# matam_qfn20.net
KiCad netlist of a schematic drawn in EAGLE
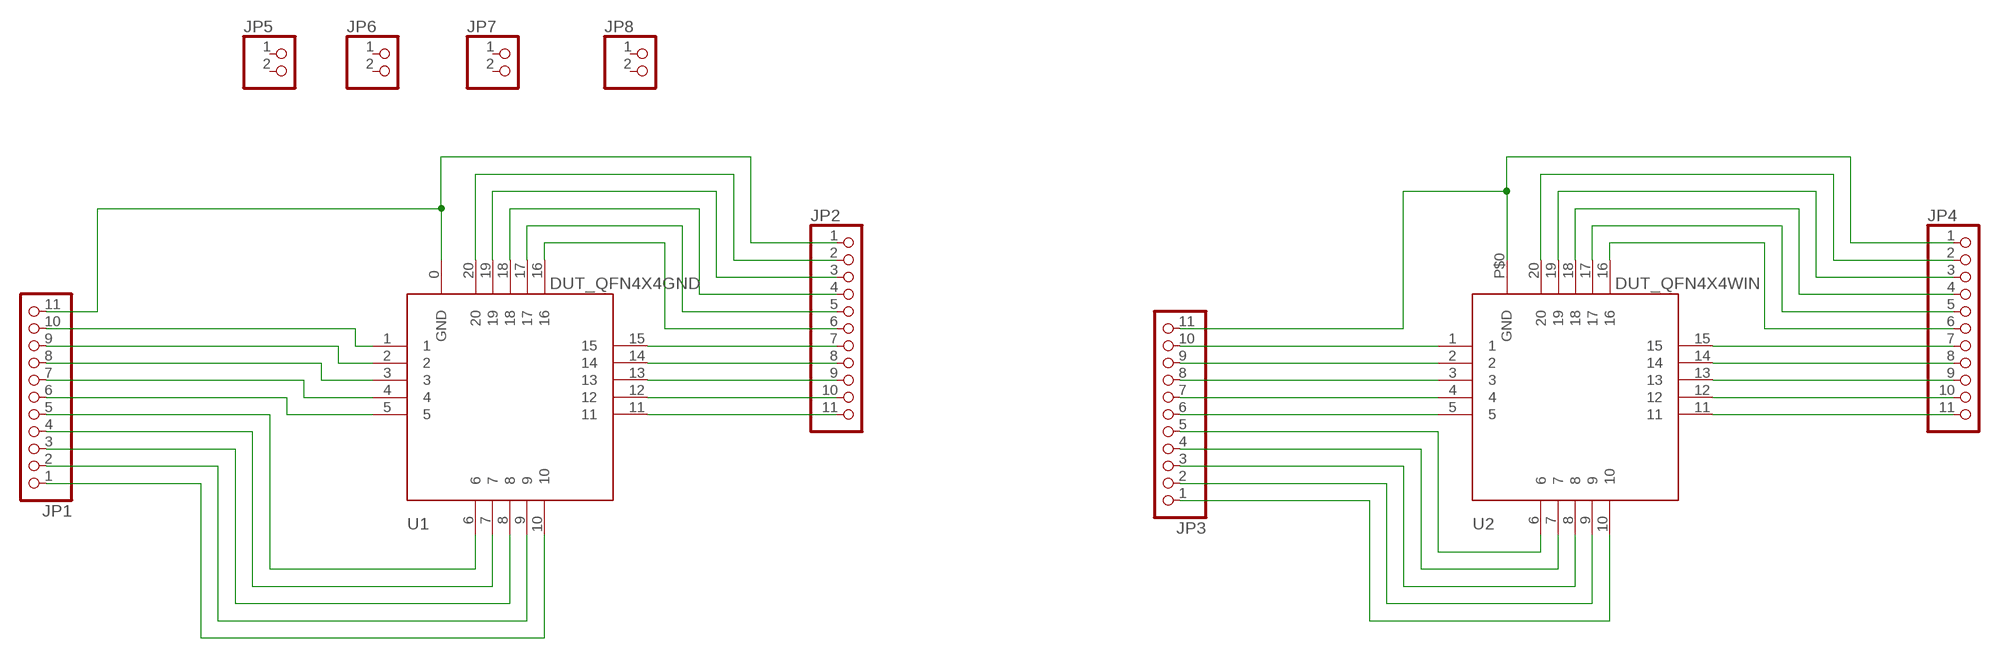
[diagram p0: schematic, sheet 1]

(export (version "E")
  (design (tool "Eeschema 10.0.6"))
  (components
    (comp (ref "JP1")
      (value "PINHD-1X11")
      (footprint "eagle-import:1X11")
      (libsource (lib "eagle-import") (part "PINHD-1X11"))
    )
    (comp (ref "JP2")
      (value "PINHD-1X11")
      (footprint "eagle-import:1X11")
      (libsource (lib "eagle-import") (part "PINHD-1X11"))
    )
    (comp (ref "JP3")
      (value "PINHD-1X11")
      (footprint "eagle-import:1X11")
      (libsource (lib "eagle-import") (part "PINHD-1X11"))
    )
    (comp (ref "JP4")
      (value "PINHD-1X11")
      (footprint "eagle-import:1X11")
      (libsource (lib "eagle-import") (part "PINHD-1X11"))
    )
    (comp (ref "JP5")
      (value "PINHD-1X2/90")
      (footprint "eagle-import:1X02_90")
      (libsource (lib "eagle-import") (part "PINHD-1X2/90"))
    )
    (comp (ref "JP6")
      (value "PINHD-1X2/90")
      (footprint "eagle-import:1X02_90")
      (libsource (lib "eagle-import") (part "PINHD-1X2/90"))
    )
    (comp (ref "JP7")
      (value "PINHD-1X2/90")
      (footprint "eagle-import:1X02_90")
      (libsource (lib "eagle-import") (part "PINHD-1X2/90"))
    )
    (comp (ref "JP8")
      (value "PINHD-1X2/90")
      (footprint "eagle-import:1X02_90")
      (libsource (lib "eagle-import") (part "PINHD-1X2/90"))
    )
    (comp (ref "U1")
      (value "DUT_QFN4X4GND")
      (footprint "eagle-import:QFN20_4X4_GND")
      (libsource (lib "eagle-import") (part "DUT_QFN4X4GND"))
    )
    (comp (ref "U2")
      (value "DUT_QFN4X4WIN")
      (footprint "eagle-import:QFN20_4X4_WINDOW")
      (libsource (lib "eagle-import") (part "DUT_QFN4X4WIN"))
    )
  )
  (nets
    (net (code "1") (name "Net-(JP1-Pad1)") (class "Default")
      (node (ref "JP1") (pin "1") (pinfunction "1_1") (pintype "passive"))
      (node (ref "U1") (pin "10") (pinfunction "10_10") (pintype "bidirectional"))
    )
    (net (code "2") (name "Net-(JP1-Pad2)") (class "Default")
      (node (ref "JP1") (pin "2") (pinfunction "2_2") (pintype "passive"))
      (node (ref "U1") (pin "9") (pinfunction "9_9") (pintype "bidirectional"))
    )
    (net (code "3") (name "Net-(JP1-Pad3)") (class "Default")
      (node (ref "JP1") (pin "3") (pinfunction "3_3") (pintype "passive"))
      (node (ref "U1") (pin "8") (pinfunction "8_8") (pintype "bidirectional"))
    )
    (net (code "4") (name "Net-(JP1-Pad4)") (class "Default")
      (node (ref "JP1") (pin "4") (pinfunction "4_4") (pintype "passive"))
      (node (ref "U1") (pin "7") (pinfunction "7_7") (pintype "bidirectional"))
    )
    (net (code "5") (name "Net-(JP1-Pad5)") (class "Default")
      (node (ref "JP1") (pin "5") (pinfunction "5_5") (pintype "passive"))
      (node (ref "U1") (pin "6") (pinfunction "6_6") (pintype "bidirectional"))
    )
    (net (code "6") (name "Net-(JP1-Pad6)") (class "Default")
      (node (ref "JP1") (pin "6") (pinfunction "6_6") (pintype "passive"))
      (node (ref "U1") (pin "5") (pinfunction "5_5") (pintype "bidirectional"))
    )
    (net (code "7") (name "Net-(JP1-Pad7)") (class "Default")
      (node (ref "JP1") (pin "7") (pinfunction "7_7") (pintype "passive"))
      (node (ref "U1") (pin "4") (pinfunction "4_4") (pintype "bidirectional"))
    )
    (net (code "8") (name "Net-(JP1-Pad8)") (class "Default")
      (node (ref "JP1") (pin "8") (pinfunction "8_8") (pintype "passive"))
      (node (ref "U1") (pin "3") (pinfunction "3_3") (pintype "bidirectional"))
    )
    (net (code "9") (name "Net-(JP1-Pad9)") (class "Default")
      (node (ref "JP1") (pin "9") (pinfunction "9_9") (pintype "passive"))
      (node (ref "U1") (pin "2") (pinfunction "2_2") (pintype "bidirectional"))
    )
    (net (code "10") (name "Net-(JP1-Pad10)") (class "Default")
      (node (ref "JP1") (pin "10") (pinfunction "10_10") (pintype "passive"))
      (node (ref "U1") (pin "1") (pinfunction "1_1") (pintype "bidirectional"))
    )
    (net (code "11") (name "Net-(JP2-Pad2)") (class "Default")
      (node (ref "JP2") (pin "2") (pinfunction "2_2") (pintype "passive"))
      (node (ref "U1") (pin "20") (pinfunction "20_20") (pintype "bidirectional"))
    )
    (net (code "12") (name "Net-(JP2-Pad3)") (class "Default")
      (node (ref "JP2") (pin "3") (pinfunction "3_3") (pintype "passive"))
      (node (ref "U1") (pin "19") (pinfunction "19_19") (pintype "bidirectional"))
    )
    (net (code "13") (name "Net-(JP2-Pad4)") (class "Default")
      (node (ref "JP2") (pin "4") (pinfunction "4_4") (pintype "passive"))
      (node (ref "U1") (pin "18") (pinfunction "18_18") (pintype "bidirectional"))
    )
    (net (code "14") (name "Net-(JP2-Pad5)") (class "Default")
      (node (ref "JP2") (pin "5") (pinfunction "5_5") (pintype "passive"))
      (node (ref "U1") (pin "17") (pinfunction "17_17") (pintype "bidirectional"))
    )
    (net (code "15") (name "Net-(JP2-Pad6)") (class "Default")
      (node (ref "JP2") (pin "6") (pinfunction "6_6") (pintype "passive"))
      (node (ref "U1") (pin "16") (pinfunction "16_16") (pintype "bidirectional"))
    )
    (net (code "16") (name "Net-(JP2-Pad7)") (class "Default")
      (node (ref "JP2") (pin "7") (pinfunction "7_7") (pintype "passive"))
      (node (ref "U1") (pin "15") (pinfunction "15_15") (pintype "bidirectional"))
    )
    (net (code "17") (name "Net-(JP2-Pad8)") (class "Default")
      (node (ref "JP2") (pin "8") (pinfunction "8_8") (pintype "passive"))
      (node (ref "U1") (pin "14") (pinfunction "14_14") (pintype "bidirectional"))
    )
    (net (code "18") (name "Net-(JP2-Pad9)") (class "Default")
      (node (ref "JP2") (pin "9") (pinfunction "9_9") (pintype "passive"))
      (node (ref "U1") (pin "13") (pinfunction "13_13") (pintype "bidirectional"))
    )
    (net (code "19") (name "Net-(JP2-Pad10)") (class "Default")
      (node (ref "JP2") (pin "10") (pinfunction "10_10") (pintype "passive"))
      (node (ref "U1") (pin "12") (pinfunction "12_12") (pintype "bidirectional"))
    )
    (net (code "20") (name "Net-(JP2-Pad11)") (class "Default")
      (node (ref "JP2") (pin "11") (pinfunction "11_11") (pintype "passive"))
      (node (ref "U1") (pin "11") (pinfunction "11_11") (pintype "bidirectional"))
    )
    (net (code "21") (name "Net-(JP3-Pad1)") (class "Default")
      (node (ref "JP3") (pin "1") (pinfunction "1_1") (pintype "passive"))
      (node (ref "U2") (pin "10") (pinfunction "10_10") (pintype "bidirectional"))
    )
    (net (code "22") (name "Net-(JP3-Pad2)") (class "Default")
      (node (ref "JP3") (pin "2") (pinfunction "2_2") (pintype "passive"))
      (node (ref "U2") (pin "9") (pinfunction "9_9") (pintype "bidirectional"))
    )
    (net (code "23") (name "Net-(JP3-Pad3)") (class "Default")
      (node (ref "JP3") (pin "3") (pinfunction "3_3") (pintype "passive"))
      (node (ref "U2") (pin "8") (pinfunction "8_8") (pintype "bidirectional"))
    )
    (net (code "24") (name "Net-(JP3-Pad4)") (class "Default")
      (node (ref "JP3") (pin "4") (pinfunction "4_4") (pintype "passive"))
      (node (ref "U2") (pin "7") (pinfunction "7_7") (pintype "bidirectional"))
    )
    (net (code "25") (name "Net-(JP3-Pad5)") (class "Default")
      (node (ref "JP3") (pin "5") (pinfunction "5_5") (pintype "passive"))
      (node (ref "U2") (pin "6") (pinfunction "6_6") (pintype "bidirectional"))
    )
    (net (code "26") (name "Net-(JP3-Pad6)") (class "Default")
      (node (ref "JP3") (pin "6") (pinfunction "6_6") (pintype "passive"))
      (node (ref "U2") (pin "5") (pinfunction "5_5") (pintype "bidirectional"))
    )
    (net (code "27") (name "Net-(JP3-Pad7)") (class "Default")
      (node (ref "JP3") (pin "7") (pinfunction "7_7") (pintype "passive"))
      (node (ref "U2") (pin "4") (pinfunction "4_4") (pintype "bidirectional"))
    )
    (net (code "28") (name "Net-(JP3-Pad8)") (class "Default")
      (node (ref "JP3") (pin "8") (pinfunction "8_8") (pintype "passive"))
      (node (ref "U2") (pin "3") (pinfunction "3_3") (pintype "bidirectional"))
    )
    (net (code "29") (name "Net-(JP3-Pad9)") (class "Default")
      (node (ref "JP3") (pin "9") (pinfunction "9_9") (pintype "passive"))
      (node (ref "U2") (pin "2") (pinfunction "2_2") (pintype "bidirectional"))
    )
    (net (code "30") (name "Net-(JP3-Pad10)") (class "Default")
      (node (ref "JP3") (pin "10") (pinfunction "10_10") (pintype "passive"))
      (node (ref "U2") (pin "1") (pinfunction "1_1") (pintype "bidirectional"))
    )
    (net (code "31") (name "Net-(JP4-Pad2)") (class "Default")
      (node (ref "JP4") (pin "2") (pinfunction "2_2") (pintype "passive"))
      (node (ref "U2") (pin "20") (pinfunction "20_20") (pintype "bidirectional"))
    )
    (net (code "32") (name "Net-(JP4-Pad3)") (class "Default")
      (node (ref "JP4") (pin "3") (pinfunction "3_3") (pintype "passive"))
      (node (ref "U2") (pin "19") (pinfunction "19_19") (pintype "bidirectional"))
    )
    (net (code "33") (name "Net-(JP4-Pad4)") (class "Default")
      (node (ref "JP4") (pin "4") (pinfunction "4_4") (pintype "passive"))
      (node (ref "U2") (pin "18") (pinfunction "18_18") (pintype "bidirectional"))
    )
    (net (code "34") (name "Net-(JP4-Pad5)") (class "Default")
      (node (ref "JP4") (pin "5") (pinfunction "5_5") (pintype "passive"))
      (node (ref "U2") (pin "17") (pinfunction "17_17") (pintype "bidirectional"))
    )
    (net (code "35") (name "Net-(JP4-Pad6)") (class "Default")
      (node (ref "JP4") (pin "6") (pinfunction "6_6") (pintype "passive"))
      (node (ref "U2") (pin "16") (pinfunction "16_16") (pintype "bidirectional"))
    )
    (net (code "36") (name "Net-(JP4-Pad7)") (class "Default")
      (node (ref "JP4") (pin "7") (pinfunction "7_7") (pintype "passive"))
      (node (ref "U2") (pin "15") (pinfunction "15_15") (pintype "bidirectional"))
    )
    (net (code "37") (name "Net-(JP4-Pad8)") (class "Default")
      (node (ref "JP4") (pin "8") (pinfunction "8_8") (pintype "passive"))
      (node (ref "U2") (pin "14") (pinfunction "14_14") (pintype "bidirectional"))
    )
    (net (code "38") (name "Net-(JP4-Pad9)") (class "Default")
      (node (ref "JP4") (pin "9") (pinfunction "9_9") (pintype "passive"))
      (node (ref "U2") (pin "13") (pinfunction "13_13") (pintype "bidirectional"))
    )
    (net (code "39") (name "Net-(JP4-Pad10)") (class "Default")
      (node (ref "JP4") (pin "10") (pinfunction "10_10") (pintype "passive"))
      (node (ref "U2") (pin "12") (pinfunction "12_12") (pintype "bidirectional"))
    )
    (net (code "40") (name "Net-(JP4-Pad11)") (class "Default")
      (node (ref "JP4") (pin "11") (pinfunction "11_11") (pintype "passive"))
      (node (ref "U2") (pin "11") (pinfunction "11_11") (pintype "bidirectional"))
    )
    (net (code "41") (name "Net-(U1-GND)") (class "Default")
      (node (ref "JP1") (pin "11") (pinfunction "11_11") (pintype "passive"))
      (node (ref "JP2") (pin "1") (pinfunction "1_1") (pintype "passive"))
      (node (ref "U1") (pin "0") (pinfunction "GND_0") (pintype "bidirectional"))
    )
    (net (code "42") (name "Net-(U2-GND)") (class "Default")
      (node (ref "JP3") (pin "11") (pinfunction "11_11") (pintype "passive"))
      (node (ref "JP4") (pin "1") (pinfunction "1_1") (pintype "passive"))
      (node (ref "U2") (pin "P$0") (pinfunction "GND_P$0") (pintype "bidirectional"))
    )
    (net (code "43") (name "unconnected-(JP5-Pad1)") (class "Default")
      (node (ref "JP5") (pin "1") (pinfunction "1_1") (pintype "passive"))
    )
    (net (code "44") (name "unconnected-(JP5-Pad2)") (class "Default")
      (node (ref "JP5") (pin "2") (pinfunction "2_2") (pintype "passive"))
    )
    (net (code "45") (name "unconnected-(JP6-Pad1)") (class "Default")
      (node (ref "JP6") (pin "1") (pinfunction "1_1") (pintype "passive"))
    )
    (net (code "46") (name "unconnected-(JP6-Pad2)") (class "Default")
      (node (ref "JP6") (pin "2") (pinfunction "2_2") (pintype "passive"))
    )
    (net (code "47") (name "unconnected-(JP7-Pad1)") (class "Default")
      (node (ref "JP7") (pin "1") (pinfunction "1_1") (pintype "passive"))
    )
    (net (code "48") (name "unconnected-(JP7-Pad2)") (class "Default")
      (node (ref "JP7") (pin "2") (pinfunction "2_2") (pintype "passive"))
    )
    (net (code "49") (name "unconnected-(JP8-Pad1)") (class "Default")
      (node (ref "JP8") (pin "1") (pinfunction "1_1") (pintype "passive"))
    )
    (net (code "50") (name "unconnected-(JP8-Pad2)") (class "Default")
      (node (ref "JP8") (pin "2") (pinfunction "2_2") (pintype "passive"))
    )
  )
)
